# motocontrolscience.net
KiCad netlist of a schematic drawn in EAGLE
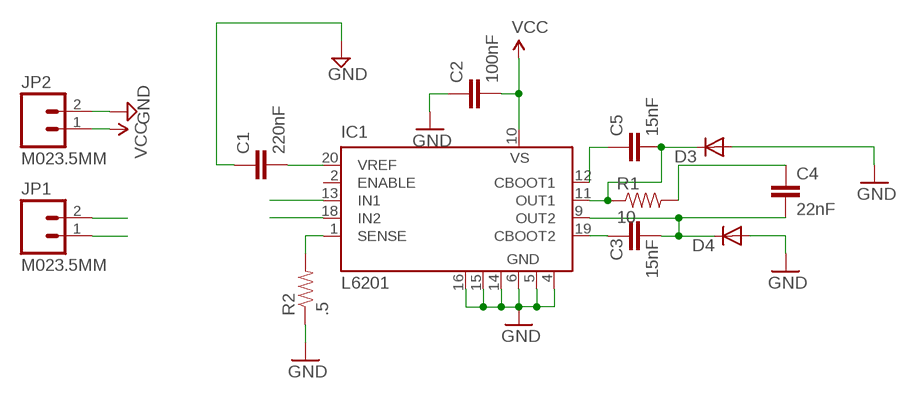
[diagram p0: schematic, sheet 1]

(export (version "E")
  (design (tool "Eeschema 10.0.6"))
  (components
    (comp (ref "C1")
      (value "220nF")
      (footprint "eagle-import:1206")
      (libsource (lib "eagle-import") (part "10UF-6.3V-20%(1206)"))
    )
    (comp (ref "C2")
      (value "100nF")
      (footprint "eagle-import:1206")
      (libsource (lib "eagle-import") (part "10UF-6.3V-20%(1206)"))
    )
    (comp (ref "C3")
      (value "15nF")
      (footprint "eagle-import:1206")
      (libsource (lib "eagle-import") (part "10UF-6.3V-20%(1206)"))
    )
    (comp (ref "C4")
      (value "22nF")
      (footprint "eagle-import:1206")
      (libsource (lib "eagle-import") (part "10UF-6.3V-20%(1206)"))
    )
    (comp (ref "C5")
      (value "15nF")
      (footprint "eagle-import:1206")
      (libsource (lib "eagle-import") (part "10UF-6.3V-20%(1206)"))
    )
    (comp (ref "D3")
      (value "DIODE-DO214BA")
      (footprint "eagle-import:DO214BA")
      (libsource (lib "eagle-import") (part "DIODE-DO214BA"))
    )
    (comp (ref "D4")
      (value "DIODE-DO214BA")
      (footprint "eagle-import:DO214BA")
      (libsource (lib "eagle-import") (part "DIODE-DO214BA"))
    )
    (comp (ref "IC1")
      (value "L6201")
      (footprint "eagle-import:SO20")
      (fields (field (name "MF") "Arrow Electronics"))
      (libsource (lib "eagle-import") (part "L6201"))
    )
    (comp (ref "JP1")
      (value "M023.5MM")
      (footprint "eagle-import:SCREWTERMINAL-3.5MM-2")
      (libsource (lib "eagle-import") (part "M023.5MM"))
    )
    (comp (ref "JP2")
      (value "M023.5MM")
      (footprint "eagle-import:SCREWTERMINAL-3.5MM-2")
      (libsource (lib "eagle-import") (part "M023.5MM"))
    )
    (comp (ref "R1")
      (value "10")
      (footprint "eagle-import:1206")
      (libsource (lib "eagle-import") (part "RESISTOR1206"))
    )
    (comp (ref "R2")
      (value ".5")
      (footprint "eagle-import:1206")
      (libsource (lib "eagle-import") (part "RESISTOR1206"))
    )
  )
  (nets
    (net (code "1") (name "/OUT1") (class "Default")
      (node (ref "C5") (pin "2") (pinfunction "2_2") (pintype "passive"))
      (node (ref "D3") (pin "C") (pinfunction "C_C") (pintype "passive"))
      (node (ref "IC1") (pin "11") (pinfunction "OUT1_11") (pintype "output"))
      (node (ref "JP1") (pin "1") (pinfunction "1_1") (pintype "passive"))
      (node (ref "R1") (pin "1") (pinfunction "1_1") (pintype "passive"))
    )
    (net (code "2") (name "/OUT2") (class "Default")
      (node (ref "C3") (pin "2") (pinfunction "2_2") (pintype "passive"))
      (node (ref "C4") (pin "2") (pinfunction "2_2") (pintype "passive"))
      (node (ref "D4") (pin "C") (pinfunction "C_C") (pintype "passive"))
      (node (ref "IC1") (pin "9") (pinfunction "OUT2_9") (pintype "output"))
      (node (ref "JP1") (pin "2") (pinfunction "2_2") (pintype "passive"))
    )
    (net (code "3") (name "GND") (class "Default")
      (node (ref "C1") (pin "1") (pinfunction "1_1") (pintype "passive"))
      (node (ref "C2") (pin "1") (pinfunction "1_1") (pintype "passive"))
      (node (ref "D3") (pin "A") (pinfunction "A_A") (pintype "passive"))
      (node (ref "D4") (pin "A") (pinfunction "A_A") (pintype "passive"))
      (node (ref "IC1") (pin "14") (pinfunction "GND_14") (pintype "power_in"))
      (node (ref "IC1") (pin "15") (pinfunction "GND_15") (pintype "power_in"))
      (node (ref "IC1") (pin "16") (pinfunction "GND_16") (pintype "power_in"))
      (node (ref "IC1") (pin "4") (pinfunction "GND_4") (pintype "power_in"))
      (node (ref "IC1") (pin "5") (pinfunction "GND_5") (pintype "power_in"))
      (node (ref "IC1") (pin "6") (pinfunction "GND_6") (pintype "power_in"))
      (node (ref "JP2") (pin "2") (pinfunction "2_2") (pintype "passive"))
      (node (ref "R2") (pin "1") (pinfunction "1_1") (pintype "passive"))
    )
    (net (code "4") (name "Net-(C4-Pad1)") (class "Default")
      (node (ref "C4") (pin "1") (pinfunction "1_1") (pintype "passive"))
      (node (ref "R1") (pin "2") (pinfunction "2_2") (pintype "passive"))
    )
    (net (code "5") (name "Net-(IC1-CBOOT1)") (class "Default")
      (node (ref "C5") (pin "1") (pinfunction "1_1") (pintype "passive"))
      (node (ref "IC1") (pin "12") (pinfunction "CBOOT1_12") (pintype "input"))
    )
    (net (code "6") (name "Net-(IC1-CBOOT2)") (class "Default")
      (node (ref "C3") (pin "1") (pinfunction "1_1") (pintype "passive"))
      (node (ref "IC1") (pin "19") (pinfunction "CBOOT2_19") (pintype "input"))
    )
    (net (code "7") (name "Net-(IC1-SENSE)") (class "Default")
      (node (ref "IC1") (pin "1") (pinfunction "SENSE_1") (pintype "input"))
      (node (ref "R2") (pin "2") (pinfunction "2_2") (pintype "passive"))
    )
    (net (code "8") (name "Net-(IC1-VREF)") (class "Default")
      (node (ref "C1") (pin "2") (pinfunction "2_2") (pintype "passive"))
      (node (ref "IC1") (pin "20") (pinfunction "VREF_20") (pintype "input"))
    )
    (net (code "9") (name "VCC") (class "Default")
      (node (ref "C2") (pin "2") (pinfunction "2_2") (pintype "passive"))
      (node (ref "IC1") (pin "10") (pinfunction "VS_10") (pintype "power_in"))
      (node (ref "JP2") (pin "1") (pinfunction "1_1") (pintype "passive"))
    )
    (net (code "10") (name "unconnected-(IC1-ENABLE-Pad2)") (class "Default")
      (node (ref "IC1") (pin "2") (pinfunction "ENABLE_2") (pintype "input"))
    )
    (net (code "11") (name "unconnected-(IC1-IN1-Pad13)") (class "Default")
      (node (ref "IC1") (pin "13") (pinfunction "IN1_13") (pintype "input"))
    )
    (net (code "12") (name "unconnected-(IC1-IN2-Pad18)") (class "Default")
      (node (ref "IC1") (pin "18") (pinfunction "IN2_18") (pintype "input"))
    )
  )
)
